# CarrierMezzanineConnectors.net
KiCad netlist of a schematic drawn in Altium Designer
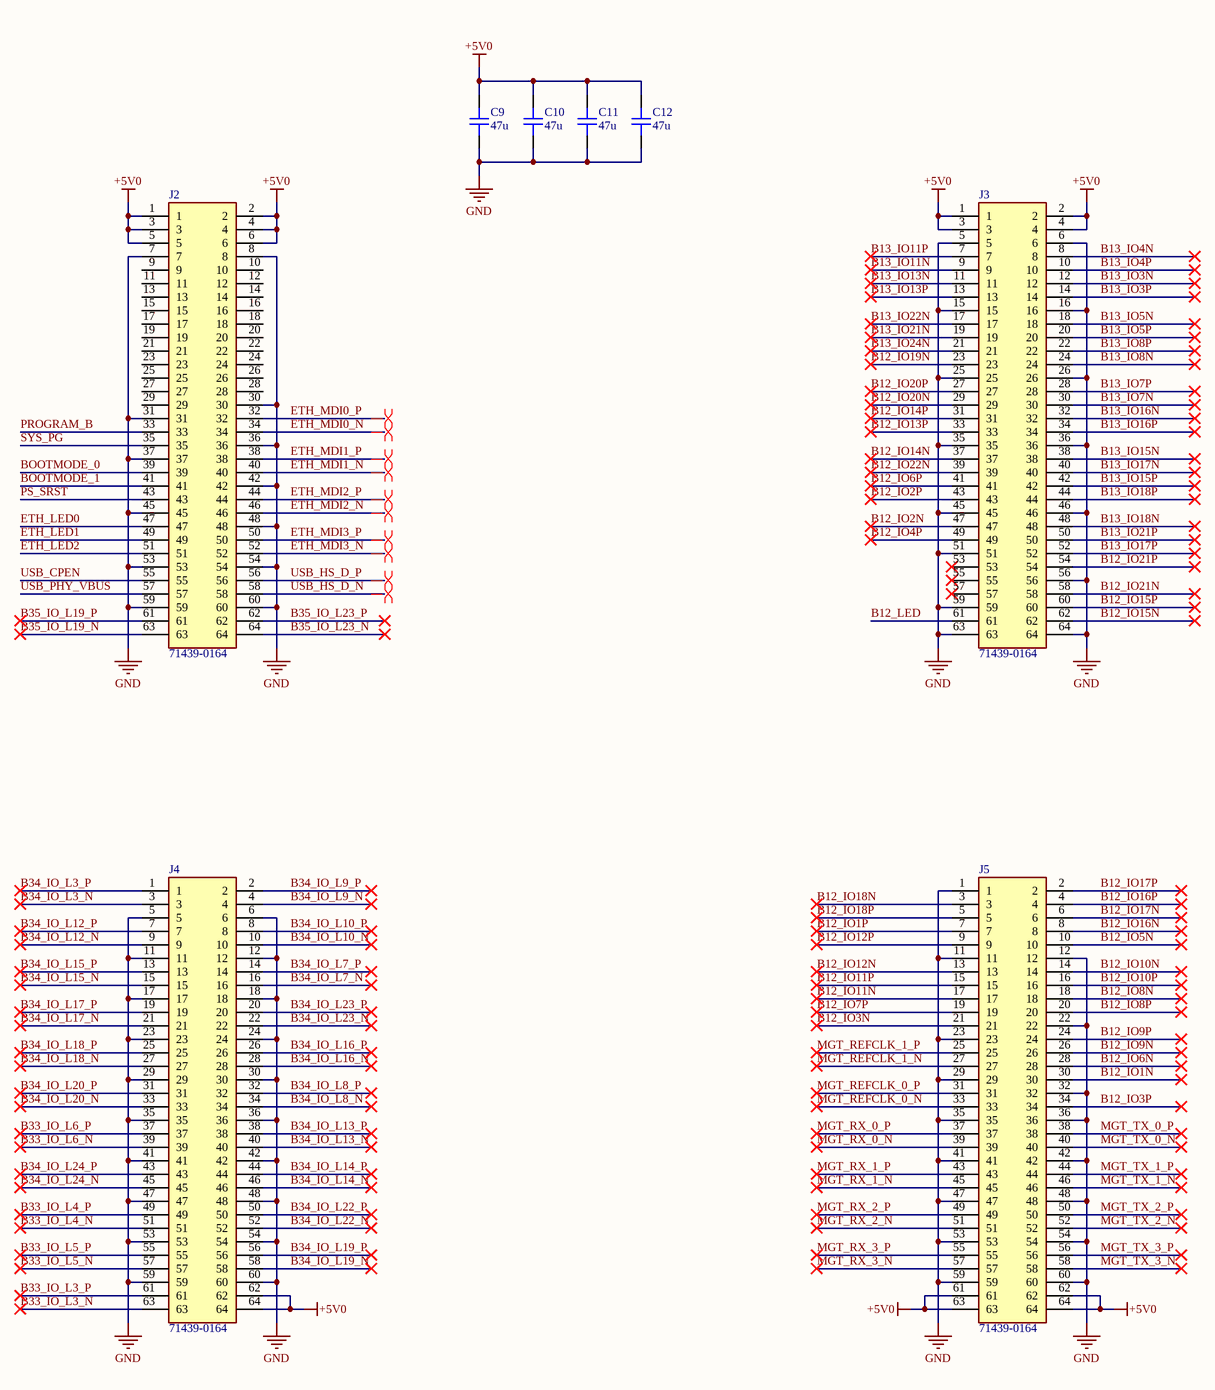
[diagram p0: CarrierMezzanineConnectors.SchDoc]

(export (version "E")
  (design (tool "Eeschema 10.0.6"))
  (components
    (comp (ref "C9")
      (value "47u")
      (footprint "CAP_1210")
      (description "Capacitor SMD 1210")
      (libsource (lib "Schematic-Lib-PhilsLab") (part "CAP_1210"))
    )
    (comp (ref "C10")
      (value "47u")
      (footprint "CAP_1210")
      (description "Capacitor SMD 1210")
      (libsource (lib "Schematic-Lib-PhilsLab") (part "CAP_1210"))
    )
    (comp (ref "C11")
      (value "47u")
      (footprint "CAP_1210")
      (description "Capacitor SMD 1210")
      (libsource (lib "Schematic-Lib-PhilsLab") (part "CAP_1210"))
    )
    (comp (ref "C12")
      (value "47u")
      (footprint "CAP_1210")
      (description "Capacitor SMD 1210")
      (libsource (lib "Schematic-Lib-PhilsLab") (part "CAP_1210"))
    )
    (comp (ref "J2")
      (value "71439-0164")
      (footprint "XC7Z030PCBLib:714390164")
      (description "Board to Board & Mezzanine Connectors PMC RECEPTACLE SMT")
      (fields (field (name "MOUSER PART NUMBER") "538-71439-0164"))
      (libsource (lib "XC7Z030SCHLib") (part "71439-0164"))
    )
    (comp (ref "J3")
      (value "71439-0164")
      (footprint "XC7Z030PCBLib:714390164")
      (description "Board to Board & Mezzanine Connectors PMC RECEPTACLE SMT")
      (fields (field (name "MOUSER PART NUMBER") "538-71439-0164"))
      (libsource (lib "XC7Z030SCHLib") (part "71439-0164"))
    )
    (comp (ref "J4")
      (value "71439-0164")
      (footprint "XC7Z030PCBLib:714390164")
      (description "Board to Board & Mezzanine Connectors PMC RECEPTACLE SMT")
      (fields (field (name "MOUSER PART NUMBER") "538-71439-0164"))
      (libsource (lib "XC7Z030SCHLib") (part "71439-0164"))
    )
    (comp (ref "J5")
      (value "71439-0164")
      (footprint "XC7Z030PCBLib:714390164")
      (description "Board to Board & Mezzanine Connectors PMC RECEPTACLE SMT")
      (fields (field (name "MOUSER PART NUMBER") "538-71439-0164"))
      (libsource (lib "XC7Z030SCHLib") (part "71439-0164"))
    )
  )
  (nets
    (net (code "1") (name "+5V0") (class "Default")
      (node (ref "C10") (pin "2") (pinfunction "2_2") (pintype "passive"))
      (node (ref "C11") (pin "2") (pinfunction "2_2") (pintype "passive"))
      (node (ref "C12") (pin "2") (pinfunction "2_2") (pintype "passive"))
      (node (ref "C9") (pin "2") (pinfunction "2_2") (pintype "passive"))
      (node (ref "J2") (pin "1") (pinfunction "1_1") (pintype "passive"))
      (node (ref "J2") (pin "2") (pinfunction "2_2") (pintype "passive"))
      (node (ref "J2") (pin "3") (pinfunction "3_3") (pintype "passive"))
      (node (ref "J2") (pin "4") (pinfunction "4_4") (pintype "passive"))
      (node (ref "J2") (pin "5") (pinfunction "5_5") (pintype "passive"))
      (node (ref "J2") (pin "6") (pinfunction "6_6") (pintype "passive"))
      (node (ref "J3") (pin "1") (pinfunction "1_1") (pintype "passive"))
      (node (ref "J3") (pin "2") (pinfunction "2_2") (pintype "passive"))
      (node (ref "J3") (pin "3") (pinfunction "3_3") (pintype "passive"))
      (node (ref "J3") (pin "4") (pinfunction "4_4") (pintype "passive"))
      (node (ref "J4") (pin "62") (pinfunction "62_62") (pintype "passive"))
      (node (ref "J4") (pin "64") (pinfunction "64_64") (pintype "passive"))
      (node (ref "J5") (pin "61") (pinfunction "61_61") (pintype "passive"))
      (node (ref "J5") (pin "62") (pinfunction "62_62") (pintype "passive"))
      (node (ref "J5") (pin "63") (pinfunction "63_63") (pintype "passive"))
      (node (ref "J5") (pin "64") (pinfunction "64_64") (pintype "passive"))
    )
    (net (code "2") (name "/B12_IO1N") (class "Default")
      (node (ref "J5") (pin "30") (pinfunction "30_30") (pintype "passive+no_connect"))
    )
    (net (code "3") (name "/B12_IO1P") (class "Default")
      (node (ref "J5") (pin "7") (pinfunction "7_7") (pintype "passive+no_connect"))
    )
    (net (code "4") (name "/B12_IO2N") (class "Default")
      (node (ref "J3") (pin "47") (pinfunction "47_47") (pintype "passive+no_connect"))
    )
    (net (code "5") (name "/B12_IO2P") (class "Default")
      (node (ref "J3") (pin "43") (pinfunction "43_43") (pintype "passive+no_connect"))
    )
    (net (code "6") (name "/B12_IO3N") (class "Default")
      (node (ref "J5") (pin "21") (pinfunction "21_21") (pintype "passive+no_connect"))
    )
    (net (code "7") (name "/B12_IO3P") (class "Default")
      (node (ref "J5") (pin "34") (pinfunction "34_34") (pintype "passive+no_connect"))
    )
    (net (code "8") (name "/B12_IO4P") (class "Default")
      (node (ref "J3") (pin "49") (pinfunction "49_49") (pintype "passive+no_connect"))
    )
    (net (code "9") (name "/B12_IO5N") (class "Default")
      (node (ref "J5") (pin "10") (pinfunction "10_10") (pintype "passive+no_connect"))
    )
    (net (code "10") (name "/B12_IO6N") (class "Default")
      (node (ref "J5") (pin "28") (pinfunction "28_28") (pintype "passive+no_connect"))
    )
    (net (code "11") (name "/B12_IO6P") (class "Default")
      (node (ref "J3") (pin "41") (pinfunction "41_41") (pintype "passive+no_connect"))
    )
    (net (code "12") (name "/B12_IO7P") (class "Default")
      (node (ref "J5") (pin "19") (pinfunction "19_19") (pintype "passive+no_connect"))
    )
    (net (code "13") (name "/B12_IO8N") (class "Default")
      (node (ref "J5") (pin "18") (pinfunction "18_18") (pintype "passive+no_connect"))
    )
    (net (code "14") (name "/B12_IO8P") (class "Default")
      (node (ref "J5") (pin "20") (pinfunction "20_20") (pintype "passive+no_connect"))
    )
    (net (code "15") (name "/B12_IO9N") (class "Default")
      (node (ref "J5") (pin "26") (pinfunction "26_26") (pintype "passive+no_connect"))
    )
    (net (code "16") (name "/B12_IO9P") (class "Default")
      (node (ref "J5") (pin "24") (pinfunction "24_24") (pintype "passive+no_connect"))
    )
    (net (code "17") (name "/B12_IO10N") (class "Default")
      (node (ref "J5") (pin "14") (pinfunction "14_14") (pintype "passive+no_connect"))
    )
    (net (code "18") (name "/B12_IO10P") (class "Default")
      (node (ref "J5") (pin "16") (pinfunction "16_16") (pintype "passive+no_connect"))
    )
    (net (code "19") (name "/B12_IO11N") (class "Default")
      (node (ref "J5") (pin "17") (pinfunction "17_17") (pintype "passive+no_connect"))
    )
    (net (code "20") (name "/B12_IO11P") (class "Default")
      (node (ref "J5") (pin "15") (pinfunction "15_15") (pintype "passive+no_connect"))
    )
    (net (code "21") (name "/B12_IO12N") (class "Default")
      (node (ref "J5") (pin "13") (pinfunction "13_13") (pintype "passive+no_connect"))
    )
    (net (code "22") (name "/B12_IO12P") (class "Default")
      (node (ref "J5") (pin "9") (pinfunction "9_9") (pintype "passive+no_connect"))
    )
    (net (code "23") (name "/B12_IO13P") (class "Default")
      (node (ref "J3") (pin "33") (pinfunction "33_33") (pintype "passive+no_connect"))
    )
    (net (code "24") (name "/B12_IO14N") (class "Default")
      (node (ref "J3") (pin "37") (pinfunction "37_37") (pintype "passive+no_connect"))
    )
    (net (code "25") (name "/B12_IO14P") (class "Default")
      (node (ref "J3") (pin "31") (pinfunction "31_31") (pintype "passive+no_connect"))
    )
    (net (code "26") (name "/B12_IO15N") (class "Default")
      (node (ref "J3") (pin "62") (pinfunction "62_62") (pintype "passive+no_connect"))
    )
    (net (code "27") (name "/B12_IO15P") (class "Default")
      (node (ref "J3") (pin "60") (pinfunction "60_60") (pintype "passive+no_connect"))
    )
    (net (code "28") (name "/B12_IO16N") (class "Default")
      (node (ref "J5") (pin "8") (pinfunction "8_8") (pintype "passive+no_connect"))
    )
    (net (code "29") (name "/B12_IO16P") (class "Default")
      (node (ref "J5") (pin "4") (pinfunction "4_4") (pintype "passive+no_connect"))
    )
    (net (code "30") (name "/B12_IO17N") (class "Default")
      (node (ref "J5") (pin "6") (pinfunction "6_6") (pintype "passive+no_connect"))
    )
    (net (code "31") (name "/B12_IO17P") (class "Default")
      (node (ref "J5") (pin "2") (pinfunction "2_2") (pintype "passive+no_connect"))
    )
    (net (code "32") (name "/B12_IO18N") (class "Default")
      (node (ref "J5") (pin "3") (pinfunction "3_3") (pintype "passive+no_connect"))
    )
    (net (code "33") (name "/B12_IO18P") (class "Default")
      (node (ref "J5") (pin "5") (pinfunction "5_5") (pintype "passive+no_connect"))
    )
    (net (code "34") (name "/B12_IO19N") (class "Default")
      (node (ref "J3") (pin "23") (pinfunction "23_23") (pintype "passive+no_connect"))
    )
    (net (code "35") (name "/B12_IO20N") (class "Default")
      (node (ref "J3") (pin "29") (pinfunction "29_29") (pintype "passive+no_connect"))
    )
    (net (code "36") (name "/B12_IO20P") (class "Default")
      (node (ref "J3") (pin "27") (pinfunction "27_27") (pintype "passive+no_connect"))
    )
    (net (code "37") (name "/B12_IO21N") (class "Default")
      (node (ref "J3") (pin "58") (pinfunction "58_58") (pintype "passive+no_connect"))
    )
    (net (code "38") (name "/B12_IO21P") (class "Default")
      (node (ref "J3") (pin "54") (pinfunction "54_54") (pintype "passive+no_connect"))
    )
    (net (code "39") (name "/B12_IO22N") (class "Default")
      (node (ref "J3") (pin "39") (pinfunction "39_39") (pintype "passive+no_connect"))
    )
    (net (code "40") (name "/B12_LED") (class "Default")
      (node (ref "J3") (pin "61") (pinfunction "61_61") (pintype "passive"))
    )
    (net (code "41") (name "/B13_IO3N") (class "Default")
      (node (ref "J3") (pin "12") (pinfunction "12_12") (pintype "passive+no_connect"))
    )
    (net (code "42") (name "/B13_IO3P") (class "Default")
      (node (ref "J3") (pin "14") (pinfunction "14_14") (pintype "passive+no_connect"))
    )
    (net (code "43") (name "/B13_IO4N") (class "Default")
      (node (ref "J3") (pin "8") (pinfunction "8_8") (pintype "passive+no_connect"))
    )
    (net (code "44") (name "/B13_IO4P") (class "Default")
      (node (ref "J3") (pin "10") (pinfunction "10_10") (pintype "passive+no_connect"))
    )
    (net (code "45") (name "/B13_IO5N") (class "Default")
      (node (ref "J3") (pin "18") (pinfunction "18_18") (pintype "passive+no_connect"))
    )
    (net (code "46") (name "/B13_IO5P") (class "Default")
      (node (ref "J3") (pin "20") (pinfunction "20_20") (pintype "passive+no_connect"))
    )
    (net (code "47") (name "/B13_IO7N") (class "Default")
      (node (ref "J3") (pin "30") (pinfunction "30_30") (pintype "passive+no_connect"))
    )
    (net (code "48") (name "/B13_IO7P") (class "Default")
      (node (ref "J3") (pin "28") (pinfunction "28_28") (pintype "passive+no_connect"))
    )
    (net (code "49") (name "/B13_IO8N") (class "Default")
      (node (ref "J3") (pin "24") (pinfunction "24_24") (pintype "passive+no_connect"))
    )
    (net (code "50") (name "/B13_IO8P") (class "Default")
      (node (ref "J3") (pin "22") (pinfunction "22_22") (pintype "passive+no_connect"))
    )
    (net (code "51") (name "/B13_IO11N") (class "Default")
      (node (ref "J3") (pin "9") (pinfunction "9_9") (pintype "passive+no_connect"))
    )
    (net (code "52") (name "/B13_IO11P") (class "Default")
      (node (ref "J3") (pin "7") (pinfunction "7_7") (pintype "passive+no_connect"))
    )
    (net (code "53") (name "/B13_IO13N") (class "Default")
      (node (ref "J3") (pin "11") (pinfunction "11_11") (pintype "passive+no_connect"))
    )
    (net (code "54") (name "/B13_IO13P") (class "Default")
      (node (ref "J3") (pin "13") (pinfunction "13_13") (pintype "passive+no_connect"))
    )
    (net (code "55") (name "/B13_IO15N") (class "Default")
      (node (ref "J3") (pin "38") (pinfunction "38_38") (pintype "passive+no_connect"))
    )
    (net (code "56") (name "/B13_IO15P") (class "Default")
      (node (ref "J3") (pin "42") (pinfunction "42_42") (pintype "passive+no_connect"))
    )
    (net (code "57") (name "/B13_IO16N") (class "Default")
      (node (ref "J3") (pin "32") (pinfunction "32_32") (pintype "passive+no_connect"))
    )
    (net (code "58") (name "/B13_IO16P") (class "Default")
      (node (ref "J3") (pin "34") (pinfunction "34_34") (pintype "passive+no_connect"))
    )
    (net (code "59") (name "/B13_IO17N") (class "Default")
      (node (ref "J3") (pin "40") (pinfunction "40_40") (pintype "passive+no_connect"))
    )
    (net (code "60") (name "/B13_IO17P") (class "Default")
      (node (ref "J3") (pin "52") (pinfunction "52_52") (pintype "passive+no_connect"))
    )
    (net (code "61") (name "/B13_IO18N") (class "Default")
      (node (ref "J3") (pin "48") (pinfunction "48_48") (pintype "passive+no_connect"))
    )
    (net (code "62") (name "/B13_IO18P") (class "Default")
      (node (ref "J3") (pin "44") (pinfunction "44_44") (pintype "passive+no_connect"))
    )
    (net (code "63") (name "/B13_IO21N") (class "Default")
      (node (ref "J3") (pin "19") (pinfunction "19_19") (pintype "passive+no_connect"))
    )
    (net (code "64") (name "/B13_IO21P") (class "Default")
      (node (ref "J3") (pin "50") (pinfunction "50_50") (pintype "passive+no_connect"))
    )
    (net (code "65") (name "/B13_IO22N") (class "Default")
      (node (ref "J3") (pin "17") (pinfunction "17_17") (pintype "passive+no_connect"))
    )
    (net (code "66") (name "/B13_IO24N") (class "Default")
      (node (ref "J3") (pin "21") (pinfunction "21_21") (pintype "passive+no_connect"))
    )
    (net (code "67") (name "/B33_IO_L3_N") (class "Default")
      (node (ref "J4") (pin "63") (pinfunction "63_63") (pintype "passive+no_connect"))
    )
    (net (code "68") (name "/B33_IO_L3_P") (class "Default")
      (node (ref "J4") (pin "61") (pinfunction "61_61") (pintype "passive+no_connect"))
    )
    (net (code "69") (name "/B33_IO_L4_N") (class "Default")
      (node (ref "J4") (pin "51") (pinfunction "51_51") (pintype "passive+no_connect"))
    )
    (net (code "70") (name "/B33_IO_L4_P") (class "Default")
      (node (ref "J4") (pin "49") (pinfunction "49_49") (pintype "passive+no_connect"))
    )
    (net (code "71") (name "/B33_IO_L5_N") (class "Default")
      (node (ref "J4") (pin "57") (pinfunction "57_57") (pintype "passive+no_connect"))
    )
    (net (code "72") (name "/B33_IO_L5_P") (class "Default")
      (node (ref "J4") (pin "55") (pinfunction "55_55") (pintype "passive+no_connect"))
    )
    (net (code "73") (name "/B33_IO_L6_N") (class "Default")
      (node (ref "J4") (pin "39") (pinfunction "39_39") (pintype "passive+no_connect"))
    )
    (net (code "74") (name "/B33_IO_L6_P") (class "Default")
      (node (ref "J4") (pin "37") (pinfunction "37_37") (pintype "passive+no_connect"))
    )
    (net (code "75") (name "/B34_IO_L3_N") (class "Default")
      (node (ref "J4") (pin "3") (pinfunction "3_3") (pintype "passive+no_connect"))
    )
    (net (code "76") (name "/B34_IO_L3_P") (class "Default")
      (node (ref "J4") (pin "1") (pinfunction "1_1") (pintype "passive+no_connect"))
    )
    (net (code "77") (name "/B34_IO_L7_N") (class "Default")
      (node (ref "J4") (pin "16") (pinfunction "16_16") (pintype "passive+no_connect"))
    )
    (net (code "78") (name "/B34_IO_L7_P") (class "Default")
      (node (ref "J4") (pin "14") (pinfunction "14_14") (pintype "passive+no_connect"))
    )
    (net (code "79") (name "/B34_IO_L8_N") (class "Default")
      (node (ref "J4") (pin "34") (pinfunction "34_34") (pintype "passive+no_connect"))
    )
    (net (code "80") (name "/B34_IO_L8_P") (class "Default")
      (node (ref "J4") (pin "32") (pinfunction "32_32") (pintype "passive+no_connect"))
    )
    (net (code "81") (name "/B34_IO_L9_N") (class "Default")
      (node (ref "J4") (pin "4") (pinfunction "4_4") (pintype "passive+no_connect"))
    )
    (net (code "82") (name "/B34_IO_L9_P") (class "Default")
      (node (ref "J4") (pin "2") (pinfunction "2_2") (pintype "passive+no_connect"))
    )
    (net (code "83") (name "/B34_IO_L10_N") (class "Default")
      (node (ref "J4") (pin "10") (pinfunction "10_10") (pintype "passive+no_connect"))
    )
    (net (code "84") (name "/B34_IO_L10_P") (class "Default")
      (node (ref "J4") (pin "8") (pinfunction "8_8") (pintype "passive+no_connect"))
    )
    (net (code "85") (name "/B34_IO_L12_N") (class "Default")
      (node (ref "J4") (pin "9") (pinfunction "9_9") (pintype "passive+no_connect"))
    )
    (net (code "86") (name "/B34_IO_L12_P") (class "Default")
      (node (ref "J4") (pin "7") (pinfunction "7_7") (pintype "passive+no_connect"))
    )
    (net (code "87") (name "/B34_IO_L13_N") (class "Default")
      (node (ref "J4") (pin "40") (pinfunction "40_40") (pintype "passive+no_connect"))
    )
    (net (code "88") (name "/B34_IO_L13_P") (class "Default")
      (node (ref "J4") (pin "38") (pinfunction "38_38") (pintype "passive+no_connect"))
    )
    (net (code "89") (name "/B34_IO_L14_N") (class "Default")
      (node (ref "J4") (pin "46") (pinfunction "46_46") (pintype "passive+no_connect"))
    )
    (net (code "90") (name "/B34_IO_L14_P") (class "Default")
      (node (ref "J4") (pin "44") (pinfunction "44_44") (pintype "passive+no_connect"))
    )
    (net (code "91") (name "/B34_IO_L15_N") (class "Default")
      (node (ref "J4") (pin "15") (pinfunction "15_15") (pintype "passive+no_connect"))
    )
    (net (code "92") (name "/B34_IO_L15_P") (class "Default")
      (node (ref "J4") (pin "13") (pinfunction "13_13") (pintype "passive+no_connect"))
    )
    (net (code "93") (name "/B34_IO_L16_N") (class "Default")
      (node (ref "J4") (pin "28") (pinfunction "28_28") (pintype "passive+no_connect"))
    )
    (net (code "94") (name "/B34_IO_L16_P") (class "Default")
      (node (ref "J4") (pin "26") (pinfunction "26_26") (pintype "passive+no_connect"))
    )
    (net (code "95") (name "/B34_IO_L17_N") (class "Default")
      (node (ref "J4") (pin "21") (pinfunction "21_21") (pintype "passive+no_connect"))
    )
    (net (code "96") (name "/B34_IO_L17_P") (class "Default")
      (node (ref "J4") (pin "19") (pinfunction "19_19") (pintype "passive+no_connect"))
    )
    (net (code "97") (name "/B34_IO_L18_N") (class "Default")
      (node (ref "J4") (pin "27") (pinfunction "27_27") (pintype "passive+no_connect"))
    )
    (net (code "98") (name "/B34_IO_L18_P") (class "Default")
      (node (ref "J4") (pin "25") (pinfunction "25_25") (pintype "passive+no_connect"))
    )
    (net (code "99") (name "/B34_IO_L19_N") (class "Default")
      (node (ref "J4") (pin "58") (pinfunction "58_58") (pintype "passive+no_connect"))
    )
    (net (code "100") (name "/B34_IO_L19_P") (class "Default")
      (node (ref "J4") (pin "56") (pinfunction "56_56") (pintype "passive+no_connect"))
    )
    (net (code "101") (name "/B34_IO_L20_N") (class "Default")
      (node (ref "J4") (pin "33") (pinfunction "33_33") (pintype "passive+no_connect"))
    )
    (net (code "102") (name "/B34_IO_L20_P") (class "Default")
      (node (ref "J4") (pin "31") (pinfunction "31_31") (pintype "passive+no_connect"))
    )
    (net (code "103") (name "/B34_IO_L22_N") (class "Default")
      (node (ref "J4") (pin "52") (pinfunction "52_52") (pintype "passive+no_connect"))
    )
    (net (code "104") (name "/B34_IO_L22_P") (class "Default")
      (node (ref "J4") (pin "50") (pinfunction "50_50") (pintype "passive+no_connect"))
    )
    (net (code "105") (name "/B34_IO_L23_N") (class "Default")
      (node (ref "J4") (pin "22") (pinfunction "22_22") (pintype "passive+no_connect"))
    )
    (net (code "106") (name "/B34_IO_L23_P") (class "Default")
      (node (ref "J4") (pin "20") (pinfunction "20_20") (pintype "passive+no_connect"))
    )
    (net (code "107") (name "/B34_IO_L24_N") (class "Default")
      (node (ref "J4") (pin "45") (pinfunction "45_45") (pintype "passive+no_connect"))
    )
    (net (code "108") (name "/B34_IO_L24_P") (class "Default")
      (node (ref "J4") (pin "43") (pinfunction "43_43") (pintype "passive+no_connect"))
    )
    (net (code "109") (name "/B35_IO_L19_N") (class "Default")
      (node (ref "J2") (pin "63") (pinfunction "63_63") (pintype "passive+no_connect"))
    )
    (net (code "110") (name "/B35_IO_L19_P") (class "Default")
      (node (ref "J2") (pin "61") (pinfunction "61_61") (pintype "passive+no_connect"))
    )
    (net (code "111") (name "/B35_IO_L23_N") (class "Default")
      (node (ref "J2") (pin "64") (pinfunction "64_64") (pintype "passive+no_connect"))
    )
    (net (code "112") (name "/B35_IO_L23_P") (class "Default")
      (node (ref "J2") (pin "62") (pinfunction "62_62") (pintype "passive+no_connect"))
    )
    (net (code "113") (name "/BOOTMODE_0") (class "Default")
      (node (ref "J2") (pin "39") (pinfunction "39_39") (pintype "passive"))
    )
    (net (code "114") (name "/BOOTMODE_1") (class "Default")
      (node (ref "J2") (pin "41") (pinfunction "41_41") (pintype "passive"))
    )
    (net (code "115") (name "/ETH_LED0") (class "Default")
      (node (ref "J2") (pin "47") (pinfunction "47_47") (pintype "passive"))
    )
    (net (code "116") (name "/ETH_LED1") (class "Default")
      (node (ref "J2") (pin "49") (pinfunction "49_49") (pintype "passive"))
    )
    (net (code "117") (name "/ETH_LED2") (class "Default")
      (node (ref "J2") (pin "51") (pinfunction "51_51") (pintype "passive"))
    )
    (net (code "118") (name "/ETH_MDI0_N") (class "Default")
      (node (ref "J2") (pin "34") (pinfunction "34_34") (pintype "passive"))
    )
    (net (code "119") (name "/ETH_MDI0_P") (class "Default")
      (node (ref "J2") (pin "32") (pinfunction "32_32") (pintype "passive"))
    )
    (net (code "120") (name "/ETH_MDI1_N") (class "Default")
      (node (ref "J2") (pin "40") (pinfunction "40_40") (pintype "passive"))
    )
    (net (code "121") (name "/ETH_MDI1_P") (class "Default")
      (node (ref "J2") (pin "38") (pinfunction "38_38") (pintype "passive"))
    )
    (net (code "122") (name "/ETH_MDI2_N") (class "Default")
      (node (ref "J2") (pin "46") (pinfunction "46_46") (pintype "passive"))
    )
    (net (code "123") (name "/ETH_MDI2_P") (class "Default")
      (node (ref "J2") (pin "44") (pinfunction "44_44") (pintype "passive"))
    )
    (net (code "124") (name "/ETH_MDI3_N") (class "Default")
      (node (ref "J2") (pin "52") (pinfunction "52_52") (pintype "passive"))
    )
    (net (code "125") (name "/ETH_MDI3_P") (class "Default")
      (node (ref "J2") (pin "50") (pinfunction "50_50") (pintype "passive"))
    )
    (net (code "126") (name "/MGT_REFCLK_0_N") (class "Default")
      (node (ref "J5") (pin "33") (pinfunction "33_33") (pintype "passive+no_connect"))
    )
    (net (code "127") (name "/MGT_REFCLK_0_P") (class "Default")
      (node (ref "J5") (pin "31") (pinfunction "31_31") (pintype "passive+no_connect"))
    )
    (net (code "128") (name "/MGT_REFCLK_1_N") (class "Default")
      (node (ref "J5") (pin "27") (pinfunction "27_27") (pintype "passive+no_connect"))
    )
    (net (code "129") (name "/MGT_REFCLK_1_P") (class "Default")
      (node (ref "J5") (pin "25") (pinfunction "25_25") (pintype "passive+no_connect"))
    )
    (net (code "130") (name "/MGT_RX_0_N") (class "Default")
      (node (ref "J5") (pin "39") (pinfunction "39_39") (pintype "passive+no_connect"))
    )
    (net (code "131") (name "/MGT_RX_0_P") (class "Default")
      (node (ref "J5") (pin "37") (pinfunction "37_37") (pintype "passive+no_connect"))
    )
    (net (code "132") (name "/MGT_RX_1_N") (class "Default")
      (node (ref "J5") (pin "45") (pinfunction "45_45") (pintype "passive+no_connect"))
    )
    (net (code "133") (name "/MGT_RX_1_P") (class "Default")
      (node (ref "J5") (pin "43") (pinfunction "43_43") (pintype "passive+no_connect"))
    )
    (net (code "134") (name "/MGT_RX_2_N") (class "Default")
      (node (ref "J5") (pin "51") (pinfunction "51_51") (pintype "passive+no_connect"))
    )
    (net (code "135") (name "/MGT_RX_2_P") (class "Default")
      (node (ref "J5") (pin "49") (pinfunction "49_49") (pintype "passive+no_connect"))
    )
    (net (code "136") (name "/MGT_RX_3_N") (class "Default")
      (node (ref "J5") (pin "57") (pinfunction "57_57") (pintype "passive+no_connect"))
    )
    (net (code "137") (name "/MGT_RX_3_P") (class "Default")
      (node (ref "J5") (pin "55") (pinfunction "55_55") (pintype "passive+no_connect"))
    )
    (net (code "138") (name "/MGT_TX_0_N") (class "Default")
      (node (ref "J5") (pin "40") (pinfunction "40_40") (pintype "passive+no_connect"))
    )
    (net (code "139") (name "/MGT_TX_0_P") (class "Default")
      (node (ref "J5") (pin "38") (pinfunction "38_38") (pintype "passive+no_connect"))
    )
    (net (code "140") (name "/MGT_TX_1_N") (class "Default")
      (node (ref "J5") (pin "46") (pinfunction "46_46") (pintype "passive+no_connect"))
    )
    (net (code "141") (name "/MGT_TX_1_P") (class "Default")
      (node (ref "J5") (pin "44") (pinfunction "44_44") (pintype "passive+no_connect"))
    )
    (net (code "142") (name "/MGT_TX_2_N") (class "Default")
      (node (ref "J5") (pin "52") (pinfunction "52_52") (pintype "passive+no_connect"))
    )
    (net (code "143") (name "/MGT_TX_2_P") (class "Default")
      (node (ref "J5") (pin "50") (pinfunction "50_50") (pintype "passive+no_connect"))
    )
    (net (code "144") (name "/MGT_TX_3_N") (class "Default")
      (node (ref "J5") (pin "58") (pinfunction "58_58") (pintype "passive+no_connect"))
    )
    (net (code "145") (name "/MGT_TX_3_P") (class "Default")
      (node (ref "J5") (pin "56") (pinfunction "56_56") (pintype "passive+no_connect"))
    )
    (net (code "146") (name "/PROGRAM_B") (class "Default")
      (node (ref "J2") (pin "33") (pinfunction "33_33") (pintype "passive"))
    )
    (net (code "147") (name "/PS_SRST") (class "Default")
      (node (ref "J2") (pin "43") (pinfunction "43_43") (pintype "passive"))
    )
    (net (code "148") (name "/SYS_PG") (class "Default")
      (node (ref "J2") (pin "35") (pinfunction "35_35") (pintype "passive"))
    )
    (net (code "149") (name "/USB_CPEN") (class "Default")
      (node (ref "J2") (pin "55") (pinfunction "55_55") (pintype "passive"))
    )
    (net (code "150") (name "/USB_HS_D_N") (class "Default")
      (node (ref "J2") (pin "58") (pinfunction "58_58") (pintype "passive"))
    )
    (net (code "151") (name "/USB_HS_D_P") (class "Default")
      (node (ref "J2") (pin "56") (pinfunction "56_56") (pintype "passive"))
    )
    (net (code "152") (name "/USB_PHY_VBUS") (class "Default")
      (node (ref "J2") (pin "57") (pinfunction "57_57") (pintype "passive"))
    )
    (net (code "153") (name "GND") (class "Default")
      (node (ref "C10") (pin "1") (pinfunction "1_1") (pintype "passive"))
      (node (ref "C11") (pin "1") (pinfunction "1_1") (pintype "passive"))
      (node (ref "C12") (pin "1") (pinfunction "1_1") (pintype "passive"))
      (node (ref "C9") (pin "1") (pinfunction "1_1") (pintype "passive"))
      (node (ref "J2") (pin "30") (pinfunction "30_30") (pintype "passive"))
      (node (ref "J2") (pin "31") (pinfunction "31_31") (pintype "passive"))
      (node (ref "J2") (pin "36") (pinfunction "36_36") (pintype "passive"))
      (node (ref "J2") (pin "37") (pinfunction "37_37") (pintype "passive"))
      (node (ref "J2") (pin "42") (pinfunction "42_42") (pintype "passive"))
      (node (ref "J2") (pin "45") (pinfunction "45_45") (pintype "passive"))
      (node (ref "J2") (pin "48") (pinfunction "48_48") (pintype "passive"))
      (node (ref "J2") (pin "53") (pinfunction "53_53") (pintype "passive"))
      (node (ref "J2") (pin "54") (pinfunction "54_54") (pintype "passive"))
      (node (ref "J2") (pin "59") (pinfunction "59_59") (pintype "passive"))
      (node (ref "J2") (pin "60") (pinfunction "60_60") (pintype "passive"))
      (node (ref "J2") (pin "7") (pinfunction "7_7") (pintype "passive"))
      (node (ref "J2") (pin "8") (pinfunction "8_8") (pintype "passive"))
      (node (ref "J3") (pin "15") (pinfunction "15_15") (pintype "passive"))
      (node (ref "J3") (pin "16") (pinfunction "16_16") (pintype "passive"))
      (node (ref "J3") (pin "25") (pinfunction "25_25") (pintype "passive"))
      (node (ref "J3") (pin "26") (pinfunction "26_26") (pintype "passive"))
      (node (ref "J3") (pin "35") (pinfunction "35_35") (pintype "passive"))
      (node (ref "J3") (pin "36") (pinfunction "36_36") (pintype "passive"))
      (node (ref "J3") (pin "45") (pinfunction "45_45") (pintype "passive"))
      (node (ref "J3") (pin "46") (pinfunction "46_46") (pintype "passive"))
      (node (ref "J3") (pin "5") (pinfunction "5_5") (pintype "passive"))
      (node (ref "J3") (pin "51") (pinfunction "51_51") (pintype "passive"))
      (node (ref "J3") (pin "56") (pinfunction "56_56") (pintype "passive"))
      (node (ref "J3") (pin "59") (pinfunction "59_59") (pintype "passive"))
      (node (ref "J3") (pin "6") (pinfunction "6_6") (pintype "passive"))
      (node (ref "J3") (pin "63") (pinfunction "63_63") (pintype "passive"))
      (node (ref "J3") (pin "64") (pinfunction "64_64") (pintype "passive"))
      (node (ref "J4") (pin "11") (pinfunction "11_11") (pintype "passive"))
      (node (ref "J4") (pin "12") (pinfunction "12_12") (pintype "passive"))
      (node (ref "J4") (pin "17") (pinfunction "17_17") (pintype "passive"))
      (node (ref "J4") (pin "18") (pinfunction "18_18") (pintype "passive"))
      (node (ref "J4") (pin "23") (pinfunction "23_23") (pintype "passive"))
      (node (ref "J4") (pin "24") (pinfunction "24_24") (pintype "passive"))
      (node (ref "J4") (pin "29") (pinfunction "29_29") (pintype "passive"))
      (node (ref "J4") (pin "30") (pinfunction "30_30") (pintype "passive"))
      (node (ref "J4") (pin "35") (pinfunction "35_35") (pintype "passive"))
      (node (ref "J4") (pin "36") (pinfunction "36_36") (pintype "passive"))
      (node (ref "J4") (pin "41") (pinfunction "41_41") (pintype "passive"))
      (node (ref "J4") (pin "42") (pinfunction "42_42") (pintype "passive"))
      (node (ref "J4") (pin "47") (pinfunction "47_47") (pintype "passive"))
      (node (ref "J4") (pin "48") (pinfunction "48_48") (pintype "passive"))
      (node (ref "J4") (pin "5") (pinfunction "5_5") (pintype "passive"))
      (node (ref "J4") (pin "53") (pinfunction "53_53") (pintype "passive"))
      (node (ref "J4") (pin "54") (pinfunction "54_54") (pintype "passive"))
      (node (ref "J4") (pin "59") (pinfunction "59_59") (pintype "passive"))
      (node (ref "J4") (pin "6") (pinfunction "6_6") (pintype "passive"))
      (node (ref "J4") (pin "60") (pinfunction "60_60") (pintype "passive"))
      (node (ref "J5") (pin "1") (pinfunction "1_1") (pintype "passive"))
      (node (ref "J5") (pin "11") (pinfunction "11_11") (pintype "passive"))
      (node (ref "J5") (pin "12") (pinfunction "12_12") (pintype "passive"))
      (node (ref "J5") (pin "22") (pinfunction "22_22") (pintype "passive"))
      (node (ref "J5") (pin "23") (pinfunction "23_23") (pintype "passive"))
      (node (ref "J5") (pin "29") (pinfunction "29_29") (pintype "passive"))
      (node (ref "J5") (pin "32") (pinfunction "32_32") (pintype "passive"))
      (node (ref "J5") (pin "35") (pinfunction "35_35") (pintype "passive"))
      (node (ref "J5") (pin "36") (pinfunction "36_36") (pintype "passive"))
      (node (ref "J5") (pin "41") (pinfunction "41_41") (pintype "passive"))
      (node (ref "J5") (pin "42") (pinfunction "42_42") (pintype "passive"))
      (node (ref "J5") (pin "47") (pinfunction "47_47") (pintype "passive"))
      (node (ref "J5") (pin "48") (pinfunction "48_48") (pintype "passive"))
      (node (ref "J5") (pin "53") (pinfunction "53_53") (pintype "passive"))
      (node (ref "J5") (pin "54") (pinfunction "54_54") (pintype "passive"))
      (node (ref "J5") (pin "59") (pinfunction "59_59") (pintype "passive"))
      (node (ref "J5") (pin "60") (pinfunction "60_60") (pintype "passive"))
    )
    (net (code "154") (name "unconnected-(J2-Pad9)") (class "Default")
      (node (ref "J2") (pin "9") (pinfunction "9_9") (pintype "passive"))
    )
    (net (code "155") (name "unconnected-(J2-Pad10)") (class "Default")
      (node (ref "J2") (pin "10") (pinfunction "10_10") (pintype "passive"))
    )
    (net (code "156") (name "unconnected-(J2-Pad11)") (class "Default")
      (node (ref "J2") (pin "11") (pinfunction "11_11") (pintype "passive"))
    )
    (net (code "157") (name "unconnected-(J2-Pad12)") (class "Default")
      (node (ref "J2") (pin "12") (pinfunction "12_12") (pintype "passive"))
    )
    (net (code "158") (name "unconnected-(J2-Pad13)") (class "Default")
      (node (ref "J2") (pin "13") (pinfunction "13_13") (pintype "passive"))
    )
    (net (code "159") (name "unconnected-(J2-Pad14)") (class "Default")
      (node (ref "J2") (pin "14") (pinfunction "14_14") (pintype "passive"))
    )
    (net (code "160") (name "unconnected-(J2-Pad15)") (class "Default")
      (node (ref "J2") (pin "15") (pinfunction "15_15") (pintype "passive"))
    )
    (net (code "161") (name "unconnected-(J2-Pad16)") (class "Default")
      (node (ref "J2") (pin "16") (pinfunction "16_16") (pintype "passive"))
    )
    (net (code "162") (name "unconnected-(J2-Pad17)") (class "Default")
      (node (ref "J2") (pin "17") (pinfunction "17_17") (pintype "passive"))
    )
    (net (code "163") (name "unconnected-(J2-Pad18)") (class "Default")
      (node (ref "J2") (pin "18") (pinfunction "18_18") (pintype "passive"))
    )
    (net (code "164") (name "unconnected-(J2-Pad19)") (class "Default")
      (node (ref "J2") (pin "19") (pinfunction "19_19") (pintype "passive"))
    )
    (net (code "165") (name "unconnected-(J2-Pad20)") (class "Default")
      (node (ref "J2") (pin "20") (pinfunction "20_20") (pintype "passive"))
    )
    (net (code "166") (name "unconnected-(J2-Pad21)") (class "Default")
      (node (ref "J2") (pin "21") (pinfunction "21_21") (pintype "passive"))
    )
    (net (code "167") (name "unconnected-(J2-Pad22)") (class "Default")
      (node (ref "J2") (pin "22") (pinfunction "22_22") (pintype "passive"))
    )
    (net (code "168") (name "unconnected-(J2-Pad23)") (class "Default")
      (node (ref "J2") (pin "23") (pinfunction "23_23") (pintype "passive"))
    )
    (net (code "169") (name "unconnected-(J2-Pad24)") (class "Default")
      (node (ref "J2") (pin "24") (pinfunction "24_24") (pintype "passive"))
    )
    (net (code "170") (name "unconnected-(J2-Pad25)") (class "Default")
      (node (ref "J2") (pin "25") (pinfunction "25_25") (pintype "passive"))
    )
    (net (code "171") (name "unconnected-(J2-Pad26)") (class "Default")
      (node (ref "J2") (pin "26") (pinfunction "26_26") (pintype "passive"))
    )
    (net (code "172") (name "unconnected-(J2-Pad27)") (class "Default")
      (node (ref "J2") (pin "27") (pinfunction "27_27") (pintype "passive"))
    )
    (net (code "173") (name "unconnected-(J2-Pad28)") (class "Default")
      (node (ref "J2") (pin "28") (pinfunction "28_28") (pintype "passive"))
    )
    (net (code "174") (name "unconnected-(J2-Pad29)") (class "Default")
      (node (ref "J2") (pin "29") (pinfunction "29_29") (pintype "passive"))
    )
    (net (code "175") (name "unconnected-(J3-Pad53)") (class "Default")
      (node (ref "J3") (pin "53") (pinfunction "53_53") (pintype "passive+no_connect"))
    )
    (net (code "176") (name "unconnected-(J3-Pad55)") (class "Default")
      (node (ref "J3") (pin "55") (pinfunction "55_55") (pintype "passive+no_connect"))
    )
    (net (code "177") (name "unconnected-(J3-Pad57)") (class "Default")
      (node (ref "J3") (pin "57") (pinfunction "57_57") (pintype "passive+no_connect"))
    )
  )
)
